# coaxial-port.net
KiCad netlist of a schematic drawn in Altium Designer
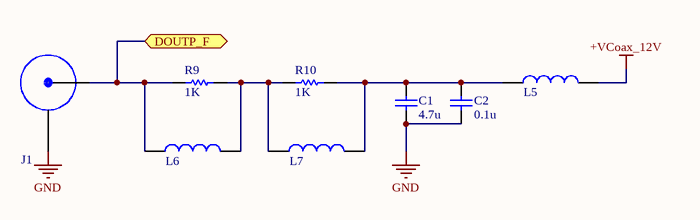
[diagram p0: coaxial-port.SchDoc]

(export (version "E")
  (design (tool "Eeschema 10.0.6"))
  (components
    (comp (ref "C1")
      (value "4.7u")
      (footprint "Cap-0603")
      (description "Capacitor")
      (fields (field (name "Comment") "X7R Ceramic") (field (name "PUBLISHER") "Altium Limited"))
      (libsource (lib "Miscellaneous Devices") (part "Cap"))
    )
    (comp (ref "C2")
      (value "0.1u")
      (footprint "Cap-0603")
      (description "Capacitor")
      (fields (field (name "Comment") "X7R Ceramic") (field (name "PUBLISHER") "Altium Limited"))
      (libsource (lib "Miscellaneous Devices") (part "Cap"))
    )
    (comp (ref "J1")
      (value "Coax Connector")
      (footprint "SMA_132134-10-ND")
      (libsource (lib "DA_Component_Library") (part "Coax Connector"))
    )
    (comp (ref "L5")
      (value "Ferrite Bead")
      (footprint "BLM18KG601SN1D")
      (libsource (lib "DA_Component_Library") (part "Ferrite Bead"))
    )
    (comp (ref "L6")
      (value "Ferrite Bead")
      (footprint "CIG21L4R7MNE")
      (libsource (lib "DA_Component_Library") (part "Ferrite Bead"))
    )
    (comp (ref "L7")
      (value "Ferrite Bead")
      (footprint "CBC3225T101MR")
      (libsource (lib "DA_Component_Library") (part "Ferrite Bead"))
    )
    (comp (ref "R9")
      (value "1K")
      (footprint "Res_0402")
      (description "Resistor")
      (fields (field (name "Comment") "Res1") (field (name "PUBLISHER") "Altium Limited"))
      (libsource (lib "Miscellaneous Devices") (part "Res1"))
    )
    (comp (ref "R10")
      (value "1K")
      (footprint "Res_0402")
      (description "Resistor")
      (fields (field (name "Comment") "Res1") (field (name "PUBLISHER") "Altium Limited"))
      (libsource (lib "Miscellaneous Devices") (part "Res1"))
    )
  )
  (nets
    (net (code "1") (name "+VCoax_12V") (class "Default")
      (node (ref "L5") (pin "2") (pinfunction "2_2") (pintype "passive"))
    )
    (net (code "2") (name "/DOUTP_F") (class "Default")
      (node (ref "J1") (pin "0") (pinfunction "0_0") (pintype "passive"))
      (node (ref "L6") (pin "1") (pinfunction "1_1") (pintype "passive"))
      (node (ref "R9") (pin "2") (pinfunction "2_2") (pintype "passive"))
    )
    (net (code "3") (name "GND") (class "Default")
      (node (ref "C1") (pin "1") (pinfunction "1_1") (pintype "passive"))
      (node (ref "C2") (pin "1") (pinfunction "1_1") (pintype "passive"))
      (node (ref "J1") (pin "1") (pinfunction "1_1") (pintype "passive"))
    )
    (net (code "4") (name "Net-(C1-Pad2)") (class "Default")
      (node (ref "C1") (pin "2") (pinfunction "2_2") (pintype "passive"))
      (node (ref "C2") (pin "2") (pinfunction "2_2") (pintype "passive"))
      (node (ref "L5") (pin "1") (pinfunction "1_1") (pintype "passive"))
      (node (ref "L7") (pin "2") (pinfunction "2_2") (pintype "passive"))
      (node (ref "R10") (pin "1") (pinfunction "1_1") (pintype "passive"))
    )
    (net (code "5") (name "Net-(L6-Pad2)") (class "Default")
      (node (ref "L6") (pin "2") (pinfunction "2_2") (pintype "passive"))
      (node (ref "L7") (pin "1") (pinfunction "1_1") (pintype "passive"))
      (node (ref "R10") (pin "2") (pinfunction "2_2") (pintype "passive"))
      (node (ref "R9") (pin "1") (pinfunction "1_1") (pintype "passive"))
    )
  )
)
